# DropCounter.net
KiCad netlist of a schematic drawn in Altium Designer
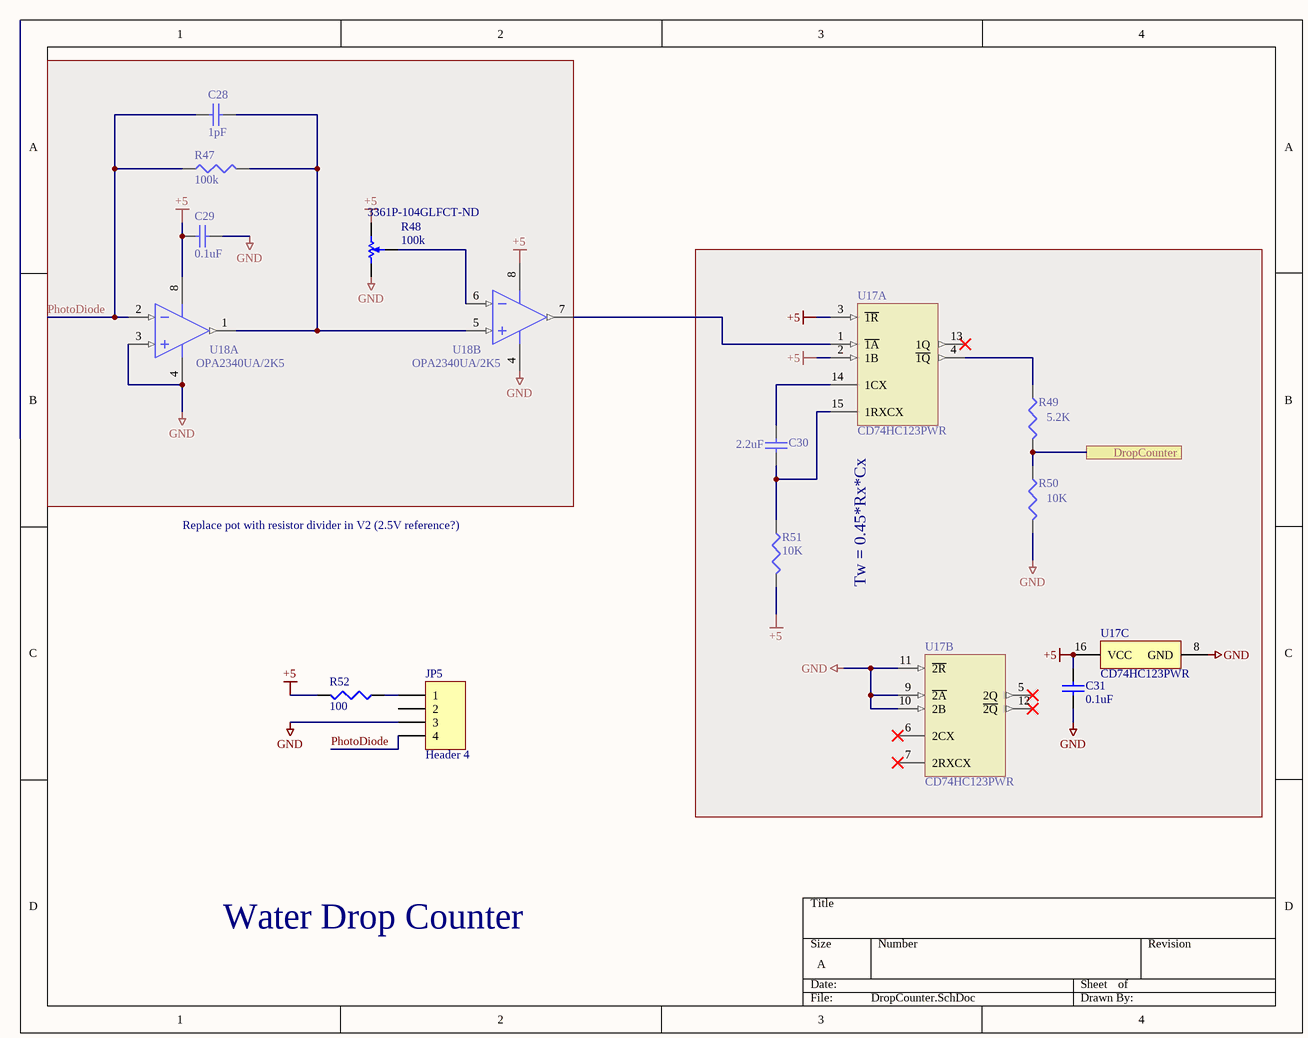
[diagram p0: DropCounter.SchDoc]

(export (version "E")
  (design (tool "Eeschema 10.0.6"))
  (components
    (comp (ref "C28")
      (value "1pF")
      (footprint "J1-0603")
      (description "CAP CER 1PF 50V C0G/NPO 0603")
      (fields (field (name "PARTNUMBER") "CC0603CRNPO9BN1R0") (field (name "PUBLISHER") "Altium Limited"))
      (libsource (lib "Miscellaneous Devices") (part "Cap Semi"))
    )
    (comp (ref "C29")
      (value "0.1uF")
      (footprint "J1-0603")
      (description "Capacitor (Semiconductor SIM Model)")
      (fields
        (field (name "PARTNUMBER") "CL10F104ZO8NNNC")
        (field (name "MANUFACTURER") "Samsung")
        (field (name "PUBLISHER") "Altium Limited")
      )
      (libsource (lib "Miscellaneous Devices") (part "Cap Semi"))
    )
    (comp (ref "C30")
      (value "2.2uF")
      (footprint "J1-0603")
      (description "Capacitor (Semiconductor SIM Model)")
      (fields
        (field (name "PARTNUMBER") "C0603C225K4PACTU")
        (field (name "MANUFACTURER") "KEMET")
        (field (name "PUBLISHER") "Altium Limited")
      )
      (libsource (lib "Miscellaneous Devices") (part "Cap Semi"))
    )
    (comp (ref "C31")
      (value "0.1uF")
      (footprint "J1-0603")
      (description "Capacitor (Semiconductor SIM Model)")
      (fields
        (field (name "PARTNUMBER") "CL10F104ZO8NNNC")
        (field (name "MANUFACTURER") "Samsung")
        (field (name "PUBLISHER") "Altium Limited")
      )
      (libsource (lib "Miscellaneous Devices") (part "Cap Semi"))
    )
    (comp (ref "JP5")
      (value "Header 4")
      (footprint "HDR1X4")
      (description "CONN HEADER R/A 4POS 2.54MM")
      (fields (field (name "PARTNUMBER") "0022053041") (field (name "PUBLISHER") "Altium Limited"))
      (libsource (lib "Miscellaneous Connectors") (part "Header 4"))
    )
    (comp (ref "R47")
      (value "100k")
      (footprint "J1-0603")
      (description "RES SMD 100K OHM 0.5% 1/16W 0603")
      (fields (field (name "PARTNUMBER") "RR0816P-104-D") (field (name "PUBLISHER") "Altium Limited"))
      (libsource (lib "Miscellaneous Devices") (part "Res3"))
    )
    (comp (ref "R48")
      (value "100k")
      (footprint "TrimPot")
      (description "TRIMMER 100K OHM 0.5W GW TOP ADJ")
      (fields
        (field (name "PARTNUMBER") "3361P-1-104GLF")
        (field (name "SUPPLIER PART NUMBER 1") "3361P-104GLFCT-ND")
        (field (name "PUBLISHER") "Altium Limited")
      )
      (libsource (lib "TrimPotSMD") (part "RPot SM"))
    )
    (comp (ref "R49")
      (value "5.2K")
      (footprint "J1-0603")
      (description "RES 5.23K OHM 1% 1/10W 0603")
      (fields (field (name "PARTNUMBER") "RMCF0603FT5K23") (field (name "PUBLISHER") "Altium Limited"))
      (libsource (lib "Miscellaneous Devices") (part "Res3"))
    )
    (comp (ref "R50")
      (value "10K")
      (footprint "J1-0603")
      (description "Resistor")
      (fields
        (field (name "PARTNUMBER") "RC0603JR-0710KL")
        (field (name "MANUFACTURER") "Yageo")
        (field (name "PUBLISHER") "Altium Limited")
      )
      (libsource (lib "Miscellaneous Devices") (part "Res3"))
    )
    (comp (ref "R51")
      (value "10K")
      (footprint "J1-0603")
      (description "Resistor")
      (fields
        (field (name "PARTNUMBER") "RC0603JR-0710KL")
        (field (name "MANUFACTURER") "Yageo")
        (field (name "PUBLISHER") "Altium Limited")
      )
      (libsource (lib "Miscellaneous Devices") (part "Res3"))
    )
    (comp (ref "R52")
      (value "100")
      (footprint "J1-0603")
      (description "RES SMD 100 OHM 1% 1/10W 0603")
      (fields (field (name "PARTNUMBER") "RC0603FR-07100RL") (field (name "PUBLISHER") "Altium Limited"))
      (libsource (lib "Miscellaneous Devices") (part "Res3"))
    )
    (comp (ref "U17")
      (value "CD74HC123PWR")
      (footprint "PW0016A_M")
      (description "High Speed CMOS Logic Dual Retriggerable Monostable Multivibrators with Reset, PW0016A, LARGE T&R")
      (fields
        (field (name "GENERIC PART NUMBER") "CD74HC123")
        (field (name "MANUFACTURER") "Texas Instruments")
      )
      (libsource (lib "Altium Content Vault") (part "TI-CDX4HCXX23-16"))
    )
    (comp (ref "U18")
      (value "OPA2340UA/2K5")
      (footprint "D0008A_L")
      (description "IC OPAMP GP 2 CIRCUIT 8SOIC")
      (fields (field (name "MANUFACTURER") "Texas Instruments"))
      (libsource (lib "Altium Content Vault") (part "TI-OPA-8_2"))
    )
  )
  (nets
    (net (code "1") (name "+5") (class "Default")
      (node (ref "C29") (pin "1") (pinfunction "1_1") (pintype "passive"))
      (node (ref "C31") (pin "1") (pinfunction "1_1") (pintype "passive"))
      (node (ref "R48") (pin "1") (pinfunction "1_1") (pintype "passive"))
      (node (ref "R51") (pin "2") (pinfunction "2_2") (pintype "passive"))
      (node (ref "R52") (pin "2") (pinfunction "2_2") (pintype "passive"))
      (node (ref "U17") (pin "16") (pinfunction "VCC_16") (pintype "power_in"))
      (node (ref "U17") (pin "2") (pinfunction "1B_2") (pintype "input"))
      (node (ref "U17") (pin "3") (pinfunction "~{1R}_3") (pintype "input"))
      (node (ref "U18") (pin "8") (pinfunction "V+_8") (pintype "power_in"))
    )
    (net (code "2") (name "/DropCounter") (class "Default")
      (node (ref "R49") (pin "2") (pinfunction "2_2") (pintype "passive"))
      (node (ref "R50") (pin "1") (pinfunction "1_1") (pintype "passive"))
    )
    (net (code "3") (name "/PhotoDiode") (class "Default")
      (node (ref "C28") (pin "1") (pinfunction "1_1") (pintype "passive"))
      (node (ref "JP5") (pin "4") (pinfunction "4_4") (pintype "passive"))
      (node (ref "R47") (pin "1") (pinfunction "1_1") (pintype "passive"))
      (node (ref "U18") (pin "2") (pinfunction "IN_A-_2") (pintype "input"))
    )
    (net (code "4") (name "GND") (class "Default")
      (node (ref "C29") (pin "2") (pinfunction "2_2") (pintype "passive"))
      (node (ref "C31") (pin "2") (pinfunction "2_2") (pintype "passive"))
      (node (ref "JP5") (pin "3") (pinfunction "3_3") (pintype "passive"))
      (node (ref "R48") (pin "3") (pinfunction "3_3") (pintype "passive"))
      (node (ref "R50") (pin "2") (pinfunction "2_2") (pintype "passive"))
      (node (ref "U17") (pin "10") (pinfunction "2B_10") (pintype "input"))
      (node (ref "U17") (pin "11") (pinfunction "~{2R}_11") (pintype "input"))
      (node (ref "U17") (pin "8") (pinfunction "GND_8") (pintype "power_in"))
      (node (ref "U17") (pin "9") (pinfunction "~{2A}_9") (pintype "input"))
      (node (ref "U18") (pin "3") (pinfunction "IN_A+_3") (pintype "input"))
      (node (ref "U18") (pin "4") (pinfunction "V-_4") (pintype "power_in"))
    )
    (net (code "5") (name "Net-(JP5-Pad1)") (class "Default")
      (node (ref "JP5") (pin "1") (pinfunction "1_1") (pintype "passive"))
      (node (ref "R52") (pin "1") (pinfunction "1_1") (pintype "passive"))
    )
    (net (code "6") (name "Net-(U17A-1CX)") (class "Default")
      (node (ref "C30") (pin "2") (pinfunction "2_2") (pintype "passive"))
      (node (ref "U17") (pin "14") (pinfunction "1CX_14") (pintype "passive"))
    )
    (net (code "7") (name "Net-(U17A-1RXCX)") (class "Default")
      (node (ref "C30") (pin "1") (pinfunction "1_1") (pintype "passive"))
      (node (ref "R51") (pin "1") (pinfunction "1_1") (pintype "passive"))
      (node (ref "U17") (pin "15") (pinfunction "1RXCX_15") (pintype "passive"))
    )
    (net (code "8") (name "Net-(U17A-~{1A})") (class "Default")
      (node (ref "U17") (pin "1") (pinfunction "~{1A}_1") (pintype "input"))
      (node (ref "U18") (pin "7") (pinfunction "OUT_B_7") (pintype "output"))
    )
    (net (code "9") (name "Net-(U17A-~{1Q})") (class "Default")
      (node (ref "R49") (pin "1") (pinfunction "1_1") (pintype "passive"))
      (node (ref "U17") (pin "4") (pinfunction "~{1Q}_4") (pintype "output"))
    )
    (net (code "10") (name "Net-(U18A-OUT_A)") (class "Default")
      (node (ref "C28") (pin "2") (pinfunction "2_2") (pintype "passive"))
      (node (ref "R47") (pin "2") (pinfunction "2_2") (pintype "passive"))
      (node (ref "U18") (pin "1") (pinfunction "OUT_A_1") (pintype "output"))
      (node (ref "U18") (pin "5") (pinfunction "IN_B+_5") (pintype "input"))
    )
    (net (code "11") (name "Net-(U18B-IN_B-)") (class "Default")
      (node (ref "R48") (pin "2") (pinfunction "2_2") (pintype "passive"))
      (node (ref "U18") (pin "6") (pinfunction "IN_B-_6") (pintype "input"))
    )
    (net (code "12") (name "unconnected-(JP5-Pad2)") (class "Default")
      (node (ref "JP5") (pin "2") (pinfunction "2_2") (pintype "passive"))
    )
    (net (code "13") (name "unconnected-(U17A-1Q-Pad13)") (class "Default")
      (node (ref "U17") (pin "13") (pinfunction "1Q_13") (pintype "output+no_connect"))
    )
    (net (code "14") (name "unconnected-(U17B-2CX-Pad6)") (class "Default")
      (node (ref "U17") (pin "6") (pinfunction "2CX_6") (pintype "passive+no_connect"))
    )
    (net (code "15") (name "unconnected-(U17B-2Q-Pad5)") (class "Default")
      (node (ref "U17") (pin "5") (pinfunction "2Q_5") (pintype "output+no_connect"))
    )
    (net (code "16") (name "unconnected-(U17B-2RXCX-Pad7)") (class "Default")
      (node (ref "U17") (pin "7") (pinfunction "2RXCX_7") (pintype "passive+no_connect"))
    )
    (net (code "17") (name "unconnected-(U17B-~{2Q}-Pad12)") (class "Default")
      (node (ref "U17") (pin "12") (pinfunction "~{2Q}_12") (pintype "output+no_connect"))
    )
  )
)
